# Termistor.net
KiCad netlist of a schematic drawn in Altium Designer
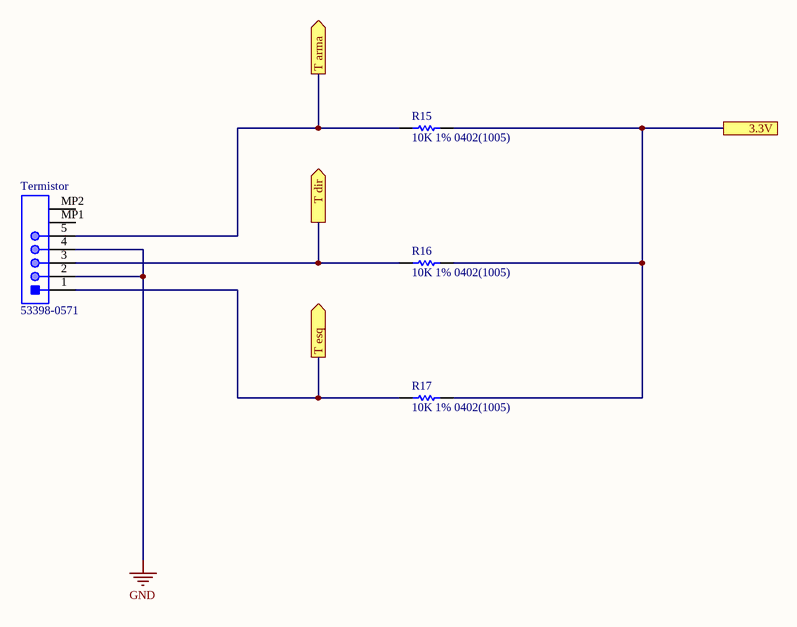
[diagram p0: Termistor.SchDoc]

(export (version "E")
  (design (tool "Eeschema 10.0.6"))
  (components
    (comp (ref "R15")
      (value "10K 1% 0402(1005)")
      (footprint "RESC0402(1005)_L")
      (description "10K 0.063W 1% 0402 (1005 Metric)  SMD                                    71-CRCW040210K0FKEDC")
      (fields (field (name "TOLERANCE") "1 %") (field (name "POWER") "0.063 W"))
      (libsource (lib "Resistor 0402 10K") (part "CMP-1011-00623-1"))
    )
    (comp (ref "R16")
      (value "10K 1% 0402(1005)")
      (footprint "RESC0402(1005)_L")
      (description "10K 0.063W 1% 0402 (1005 Metric)  SMD                                     71-CRCW040210K0FKEDC")
      (fields (field (name "TOLERANCE") "1 %") (field (name "POWER") "0.063 W"))
      (libsource (lib "Resistor 0402 10K") (part "CMP-1011-00623-1"))
    )
    (comp (ref "R17")
      (value "10K 1% 0402(1005)")
      (footprint "RESC0402(1005)_L")
      (description "10K 0.063W 1% 0402 (1005 Metric)  SMD                                        71-CRCW040210K0FKEDC")
      (fields (field (name "TOLERANCE") "1 %") (field (name "POWER") "0.063 W"))
      (libsource (lib "Resistor 0402 10K") (part "CMP-1011-00623-1"))
    )
    (comp (ref "Termistor")
      (value "53398-0571")
      (footprint "MOLX-53398-0571-5_V")
      (description "Male Header, Pitch 1.25 mm, 1 x 5 Postion, Height 4.7 mm, -40 to 85 degC, RoHS, Tape and Reel")
      (fields (field (name "MANUFACTURER") "Molex"))
      (libsource (lib "Moles_53398-0571") (part "CMP-2000-05250-1"))
    )
  )
  (nets
    (net (code "1") (name "/3.3V") (class "Default")
      (node (ref "R15") (pin "2") (pinfunction "2_2") (pintype "passive"))
      (node (ref "R16") (pin "2") (pinfunction "2_2") (pintype "passive"))
      (node (ref "R17") (pin "2") (pinfunction "2_2") (pintype "passive"))
    )
    (net (code "2") (name "/T arma") (class "Default")
      (node (ref "R15") (pin "1") (pinfunction "1_1") (pintype "passive"))
      (node (ref "Termistor") (pin "5") (pinfunction "5_5") (pintype "passive"))
    )
    (net (code "3") (name "/T dir") (class "Default")
      (node (ref "R16") (pin "1") (pinfunction "1_1") (pintype "passive"))
      (node (ref "Termistor") (pin "3") (pinfunction "3_3") (pintype "passive"))
    )
    (net (code "4") (name "/T esq") (class "Default")
      (node (ref "R17") (pin "1") (pinfunction "1_1") (pintype "passive"))
      (node (ref "Termistor") (pin "1") (pinfunction "1_1") (pintype "passive"))
    )
    (net (code "5") (name "GND") (class "Default")
      (node (ref "Termistor") (pin "2") (pinfunction "2_2") (pintype "passive"))
      (node (ref "Termistor") (pin "4") (pinfunction "4_4") (pintype "passive"))
    )
    (net (code "6") (name "unconnected-(Termistor-PadMP1)") (class "Default")
      (node (ref "Termistor") (pin "MP1") (pinfunction "MP1_MP1") (pintype "passive"))
    )
    (net (code "7") (name "unconnected-(Termistor-PadMP2)") (class "Default")
      (node (ref "Termistor") (pin "MP2") (pinfunction "MP2_MP2") (pintype "passive"))
    )
  )
)
